# 06_GBE_SDCARD.net
KiCad netlist of a schematic drawn in Altium Designer
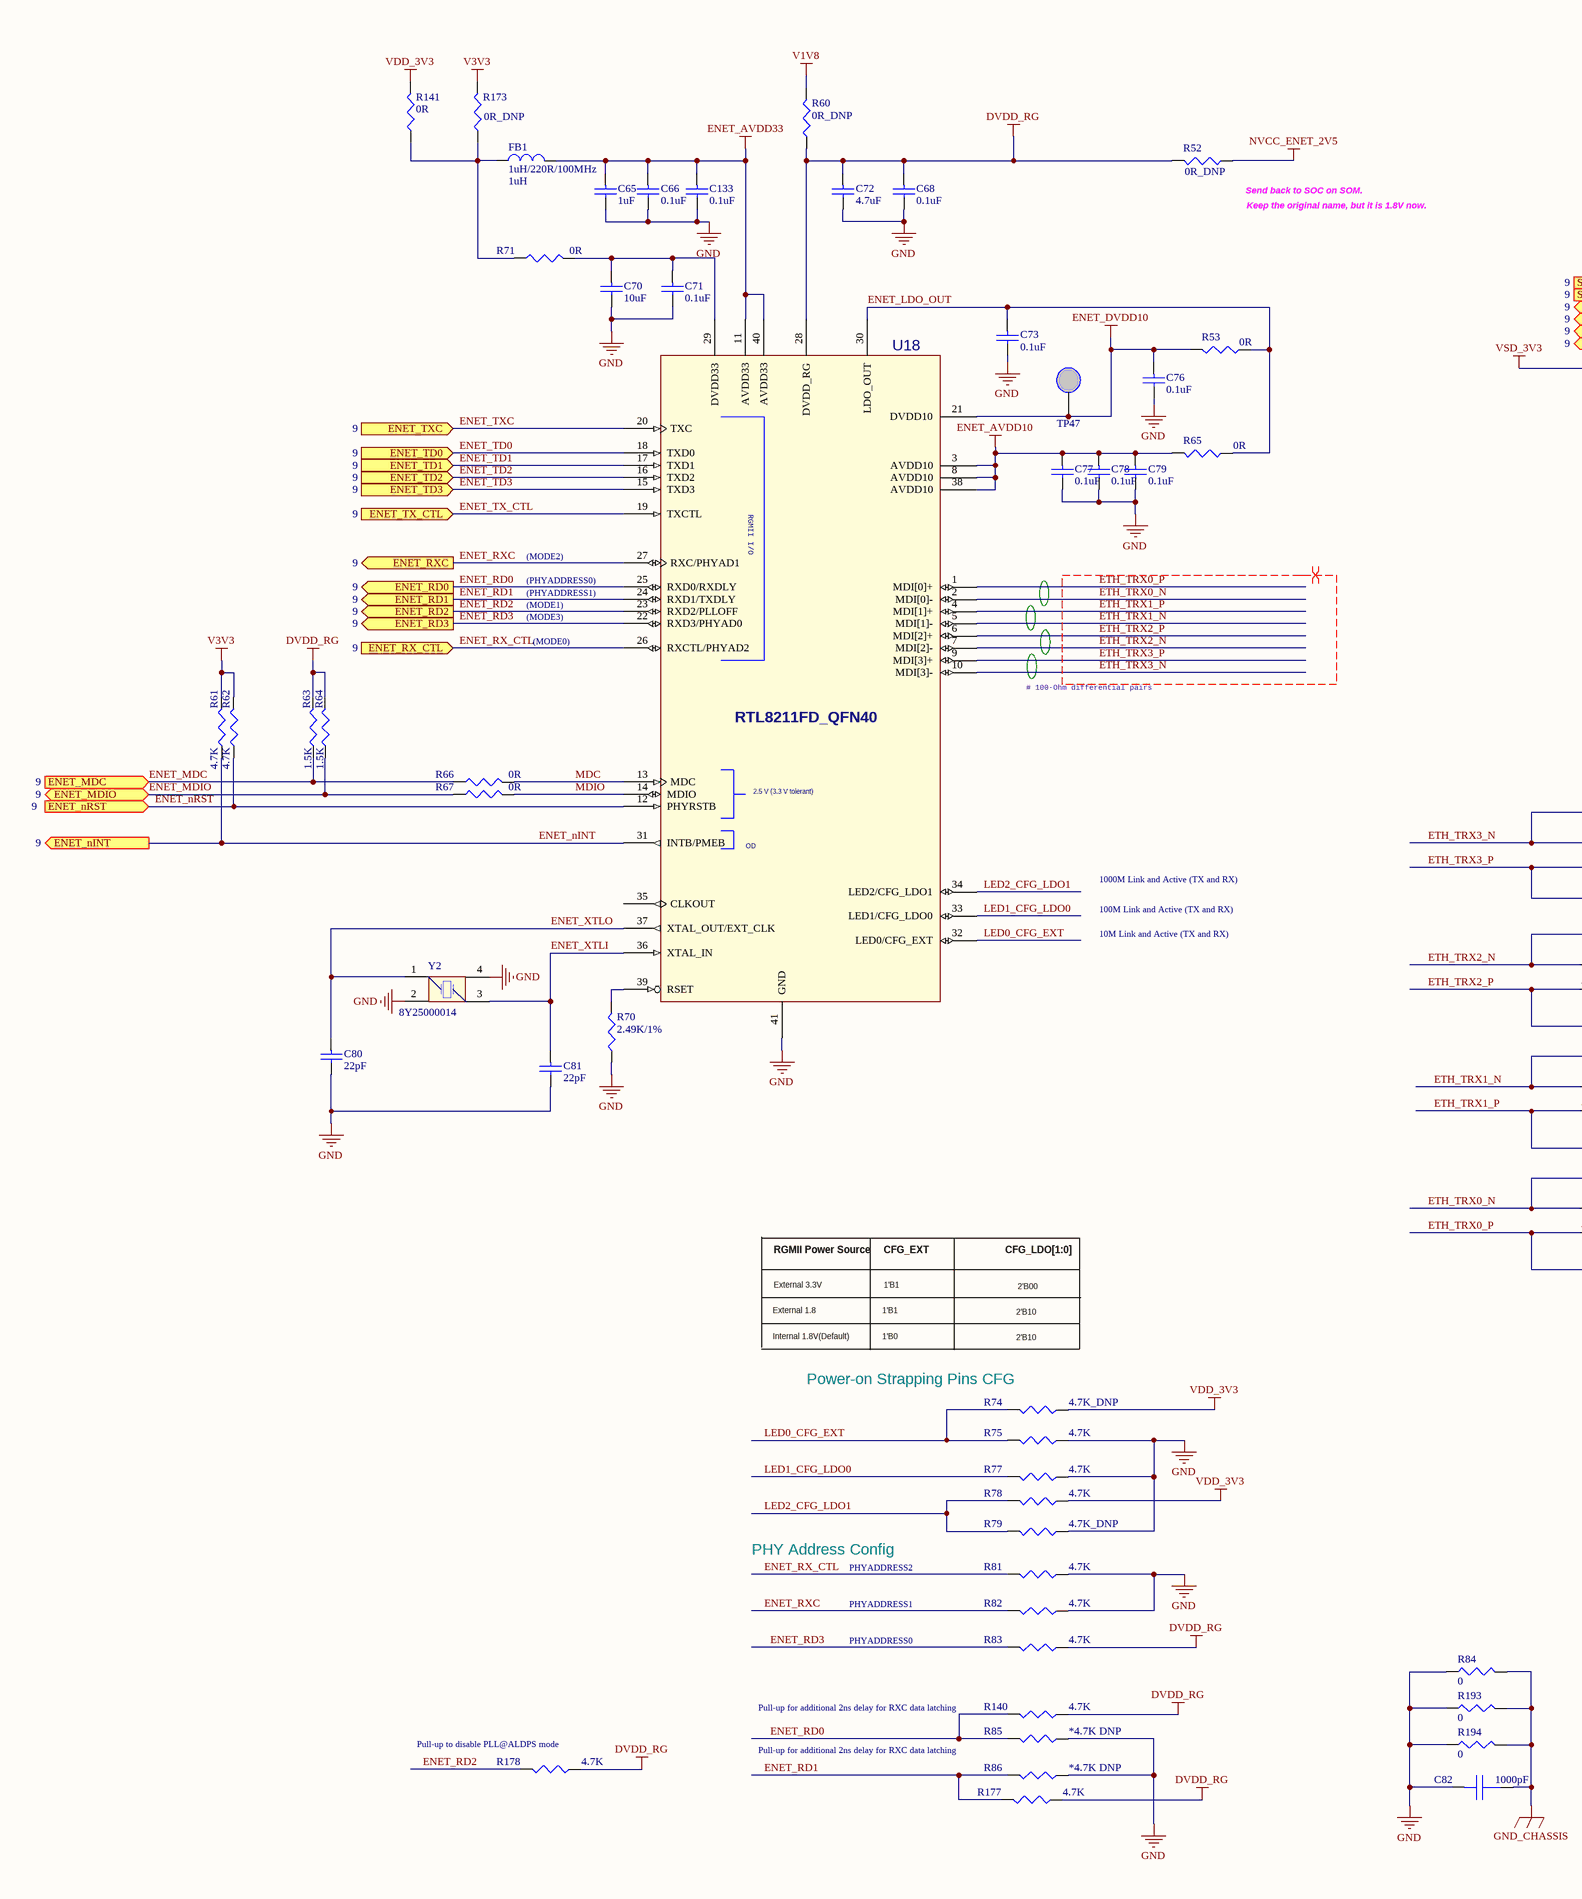
[diagram p0: 06_GBE_SDCARD.SchDoc, left]
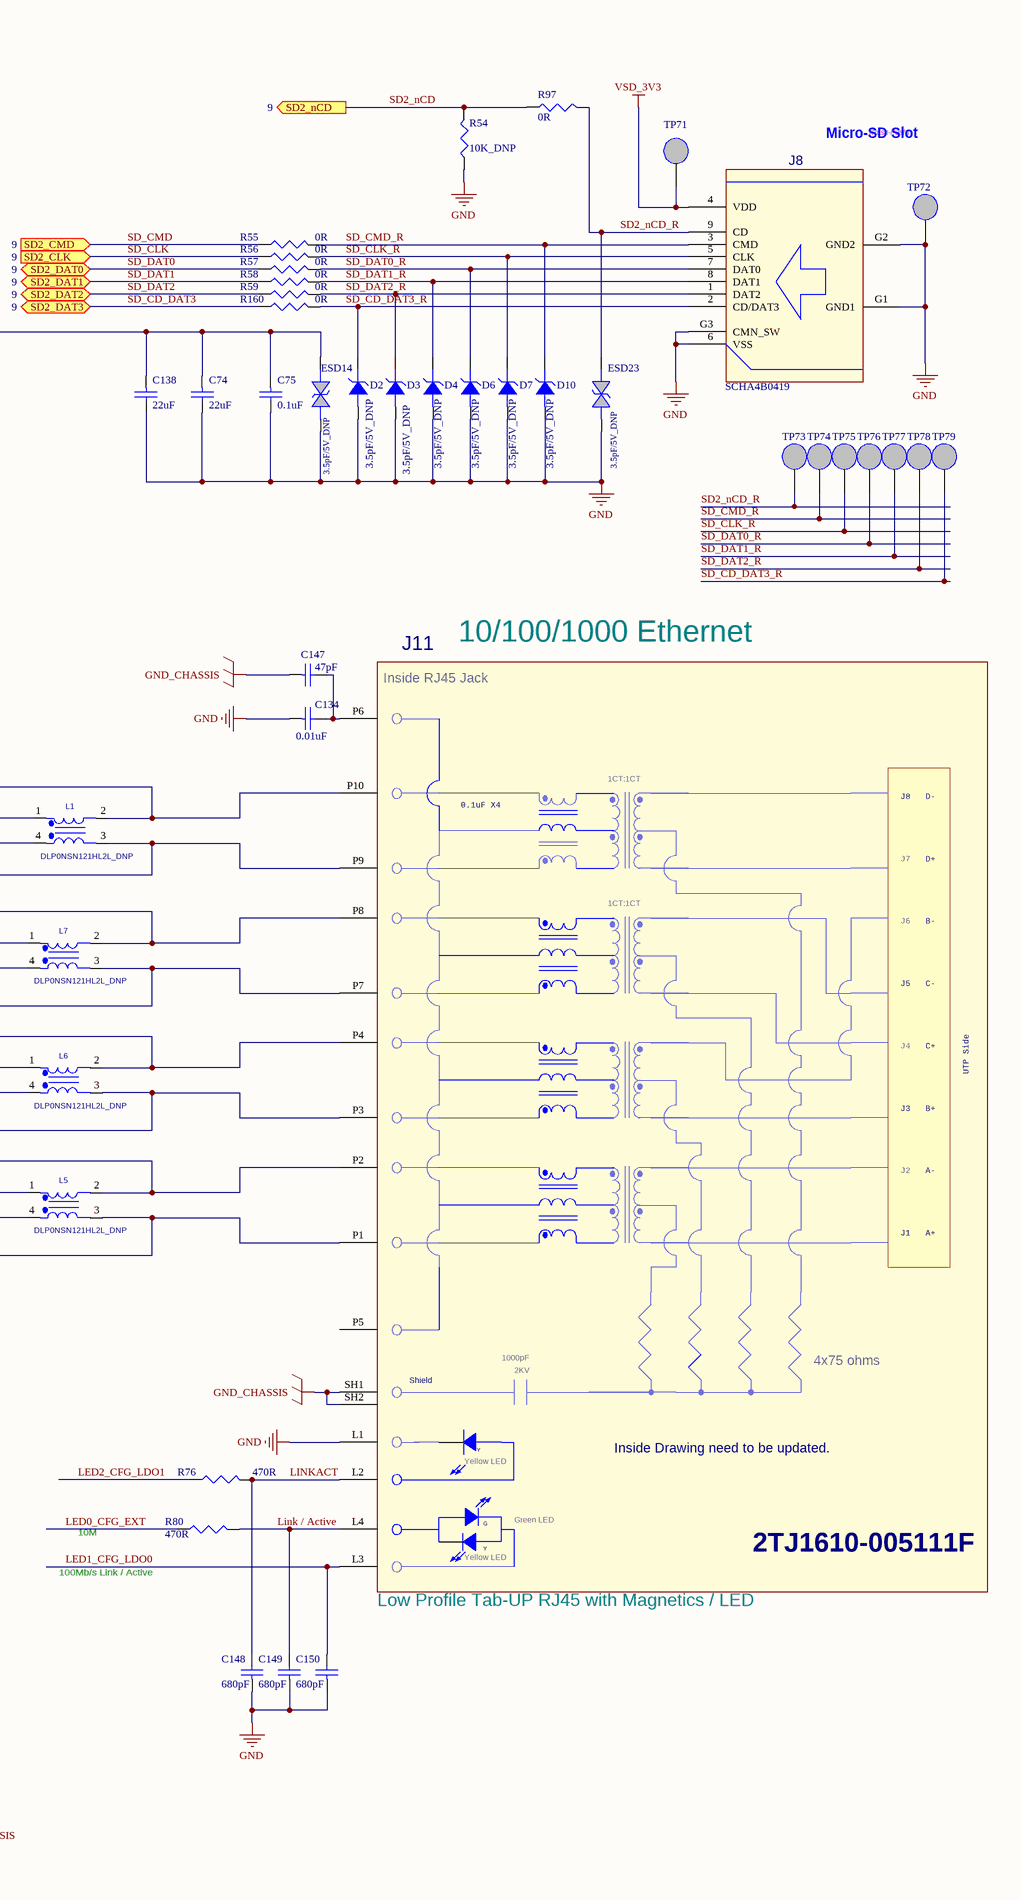
[diagram p1: 06_GBE_SDCARD.SchDoc, right]

(export (version "E")
  (design (tool "Eeschema 10.0.6"))
  (components
    (comp (ref "C65")
      (value "1uF")
      (footprint "0201")
      (description "CAP CER 1UF 6.3V 20% X5R 0201")
      (fields (field (name "MPN") "C0603X5R0J105M030BC") (field (name "Comment") "1uF/6.3V"))
      (libsource (lib "links") (part "CAP_0201_1.0uF"))
    )
    (comp (ref "C66")
      (value "0.1uF")
      (footprint "0201")
      (description "CAP CER 0.1UF 10V 10% X5R 0201")
      (fields (field (name "MPN") "C0603X5R1A104K030BC") (field (name "Comment") "0.1uF/10V"))
      (libsource (lib "links") (part "CAP_0201_0.1uF"))
    )
    (comp (ref "C68")
      (value "0.1uF")
      (footprint "0201")
      (description "CAP CER 0.1UF 10V 10% X5R 0201")
      (fields (field (name "MPN") "C0603X5R1A104K030BC") (field (name "Comment") "0.1uF/10V"))
      (libsource (lib "links") (part "CAP_0201_0.1uF"))
    )
    (comp (ref "C70")
      (value "10uF")
      (footprint "0402")
      (description "CAP CER 10UF 10V 20% X5R 0402")
      (fields (field (name "MPN") "CL05A106MP5NUNC") (field (name "Comment") "10uF/10V"))
      (libsource (lib "links") (part "CAP_0402_10uF"))
    )
    (comp (ref "C71")
      (value "0.1uF")
      (footprint "0201")
      (description "CAP CER 0.1UF 10V 10% X5R 0201")
      (fields (field (name "MPN") "C0603X5R1A104K030BC") (field (name "Comment") "0.1uF/10V"))
      (libsource (lib "links") (part "CAP_0201_0.1uF"))
    )
    (comp (ref "C72")
      (value "4.7uF")
      (footprint "0402")
      (description "CAP CER 4.7UF 10V 20% X5R 0402")
      (fields (field (name "MPN") "C1005X5R1A475M050BC") (field (name "Comment") "4.7uF/10V"))
      (libsource (lib "links") (part "CAP_0402_4.7uF"))
    )
    (comp (ref "C73")
      (value "0.1uF")
      (footprint "0201")
      (description "CAP CER 0.1UF 10V 10% X5R 0201")
      (fields (field (name "MPN") "C0603X5R1A104K030BC") (field (name "Comment") "0.1uF/10V"))
      (libsource (lib "links") (part "CAP_0201_0.1uF"))
    )
    (comp (ref "C74")
      (value "22uF")
      (footprint "0603")
      (description "CAP CER 22UF 6.3V 10% X5R 0603")
      (fields (field (name "MPN") "CL10A226KQ8NRNE") (field (name "Comment") "22uF/10V"))
      (libsource (lib "links") (part "CAP_0603_22uF"))
    )
    (comp (ref "C75")
      (value "0.1uF")
      (footprint "0201")
      (description "CAP CER 0.1UF 10V 10% X5R 0201")
      (fields (field (name "MPN") "C0603X5R1A104K030BC") (field (name "Comment") "0.1uF/10V"))
      (libsource (lib "links") (part "CAP_0201_0.1uF"))
    )
    (comp (ref "C76")
      (value "0.1uF")
      (footprint "0201")
      (description "CAP CER 0.1UF 10V 10% X5R 0201")
      (fields (field (name "MPN") "C0603X5R1A104K030BC") (field (name "Comment") "0.1uF/10V"))
      (libsource (lib "links") (part "CAP_0201_0.1uF"))
    )
    (comp (ref "C77")
      (value "0.1uF")
      (footprint "0201")
      (description "CAP CER 0.1UF 10V 10% X5R 0201")
      (fields (field (name "MPN") "C0603X5R1A104K030BC") (field (name "Comment") "0.1uF/10V"))
      (libsource (lib "links") (part "CAP_0201_0.1uF"))
    )
    (comp (ref "C78")
      (value "0.1uF")
      (footprint "0201")
      (description "CAP CER 0.1UF 10V 10% X5R 0201")
      (fields (field (name "MPN") "C0603X5R1A104K030BC") (field (name "Comment") "0.1uF/10V"))
      (libsource (lib "links") (part "CAP_0201_0.1uF"))
    )
    (comp (ref "C79")
      (value "0.1uF")
      (footprint "0201")
      (description "CAP CER 0.1UF 10V 10% X5R 0201")
      (fields (field (name "MPN") "C0603X5R1A104K030BC") (field (name "Comment") "0.1uF/10V"))
      (libsource (lib "links") (part "CAP_0201_0.1uF"))
    )
    (comp (ref "C80")
      (value "22pF")
      (footprint "0201")
      (description "CAP CER 22pF 6.3V 2% C0G NP0 0201")
      (fields (field (name "MPN") "GJM0335C0J220GB01D") (field (name "Comment") "22pF/6.3V"))
      (libsource (lib "links") (part "CAP_0201_22pF"))
    )
    (comp (ref "C81")
      (value "22pF")
      (footprint "0201")
      (description "CAP CER 22pF 6.3V 2% C0G NP0 0201")
      (fields (field (name "MPN") "GJM0335C0J220GB01D") (field (name "Comment") "22pF/6.3V"))
      (libsource (lib "links") (part "CAP_0201_22pF"))
    )
    (comp (ref "C82")
      (value "1000pF")
      (footprint "1206")
      (description "CAP CER 1000PF 2KV 10% 1206 X7R")
      (fields (field (name "MPN") "CC1206KKX7RDBB102") (field (name "Comment") "1000pF/2KV"))
      (libsource (lib "links") (part "CAP_1206_1000pF_2KV"))
    )
    (comp (ref "C133")
      (value "0.1uF")
      (footprint "0201")
      (description "CAP CER 0.1UF 10V 10% X5R 0201")
      (fields (field (name "MPN") "C0603X5R1A104K030BC") (field (name "Comment") "0.1uF/10V"))
      (libsource (lib "links") (part "CAP_0201_0.1uF"))
    )
    (comp (ref "C134")
      (value "0.01uF")
      (footprint "0201")
      (description "CAP CHIP 0.01UF 25V(+-10%,X7R,0201)")
      (fields (field (name "MPN") "GRM033R71E103K") (field (name "Comment") "0.01uF/25V"))
      (libsource (lib "links") (part "CAP_0201_0.1uF"))
    )
    (comp (ref "C138")
      (value "22uF")
      (footprint "0603")
      (description "CAP CER 22UF 6.3V 10% X5R 0603")
      (fields (field (name "MPN") "CL10A226KQ8NRNE") (field (name "Comment") "22uF/10V"))
      (libsource (lib "links") (part "CAP_0603_22uF"))
    )
    (comp (ref "C147")
      (value "47pF")
      (footprint "0201")
      (description "CAP CER 47PF 25V 0201")
      (fields (field (name "MPN") "GRM0335C1E470FA01D") (field (name "Comment") "47pF/25V"))
      (libsource (lib "links") (part "CAP_0201_47pF"))
    )
    (comp (ref "C148")
      (value "680pF")
      (footprint "0201")
      (description "CAP CHIP 680PF 25V(+-10%,X7R,0201)")
      (fields (field (name "MPN") "GRM033R71E681K") (field (name "Comment") "680PF 25V"))
      (libsource (lib "links") (part "CAP_0201_1.0nF"))
    )
    (comp (ref "C149")
      (value "680pF")
      (footprint "0201")
      (description "CAP CHIP 680PF 25V(+-10%,X7R,0201)")
      (fields (field (name "MPN") "GRM033R71E681K") (field (name "Comment") "680PF 25V"))
      (libsource (lib "links") (part "CAP_0201_1.0nF"))
    )
    (comp (ref "C150")
      (value "680pF")
      (footprint "0201")
      (description "CAP CHIP 680PF 25V(+-10%,X7R,0201)")
      (fields (field (name "MPN") "GRM033R71E681K") (field (name "Comment") "680PF 25V"))
      (libsource (lib "links") (part "CAP_0201_1.0nF"))
    )
    (comp (ref "D2")
      (value "3.5pF/5V_DNP")
      (footprint "0201-Diode")
      (description "TVS DIODE 3V ST0201")
      (fields (field (name "MPN") "DESD5V0V1BCSP-7"))
      (libsource (lib "links") (part "Diode-ESDALC6V1-1U2"))
    )
    (comp (ref "D3")
      (value "3.5pF/5V_DNP")
      (footprint "0201-Diode")
      (description "TVS DIODE 3V ST0201")
      (fields (field (name "MPN") "DESD5V0V1BCSP-7"))
      (libsource (lib "links") (part "Diode-ESDALC6V1-1U2"))
    )
    (comp (ref "D4")
      (value "3.5pF/5V_DNP")
      (footprint "0201-Diode")
      (description "TVS DIODE 3V ST0201")
      (fields (field (name "MPN") "DESD5V0V1BCSP-7"))
      (libsource (lib "links") (part "Diode-ESDALC6V1-1U2"))
    )
    (comp (ref "D6")
      (value "3.5pF/5V_DNP")
      (footprint "0201-Diode")
      (description "TVS DIODE 3V ST0201")
      (fields (field (name "MPN") "DESD5V0V1BCSP-7"))
      (libsource (lib "links") (part "Diode-ESDALC6V1-1U2"))
    )
    (comp (ref "D7")
      (value "3.5pF/5V_DNP")
      (footprint "0201-Diode")
      (description "TVS DIODE 3V ST0201")
      (fields (field (name "MPN") "DESD5V0V1BCSP-7"))
      (libsource (lib "links") (part "Diode-ESDALC6V1-1U2"))
    )
    (comp (ref "D10")
      (value "3.5pF/5V_DNP")
      (footprint "0201-Diode")
      (description "TVS DIODE 3V ST0201")
      (fields (field (name "MPN") "DESD5V0V1BCSP-7"))
      (libsource (lib "links") (part "Diode-ESDALC6V1-1U2"))
    )
    (comp (ref "ESD14")
      (value "3.5pF/5V_DNP")
      (footprint "0201")
      (description "DIODE TVS 15kV 10V 50A 8pF SMT RoHS")
      (fields (field (name "MPN") "DESD5V0V1BCSP-7"))
      (libsource (lib "links") (part "DIODE BI-DIR TRIG"))
    )
    (comp (ref "ESD23")
      (value "3.5pF/5V_DNP")
      (footprint "0201")
      (description "DIODE TVS 15kV 10V 50A 8pF SMT RoHS")
      (fields (field (name "MPN") "DESD5V0V1BCSP-7"))
      (libsource (lib "links") (part "DIODE BI-DIR TRIG"))
    )
    (comp (ref "FB1")
      (value "1uH/220R/100MHz")
      (footprint "0603")
      (description "FERRITE CHIP 220 OHM 2.0A 0603")
      (fields (field (name "ALTIUM_VALUE") "1uH") (field (name "MPN") "BLM18EG221SN1D"))
      (libsource (lib "SpacePark") (part "INDUCTOR_BLM18EG221SN1D"))
    )
    (comp (ref "J8")
      (value "SCHA4B0419")
      (footprint "CON9_SDCARD_8PIN_SCHA4B0419")
      (description "CON SD CARD PUSH SMT 1.32mm 8pin")
      (fields (field (name "SUPPLIER PART NUMBER 1") "SCHA4B0419"))
      (libsource (lib "SpacePark") (part "CONN_MICRO_SDCARD_8P_ALPS"))
    )
    (comp (ref "J11")
      (value "2TJ1610-005111F")
      (footprint "RJ45-LED-2TJ1610-005111F")
      (description "CON 10 RJ45 SKT RA TH WITH G/Y LEDS 50MIL SP 611H -- 120L")
      (libsource (lib "SpacePark") (part "RJ45_Singatron_2TJ1610-005111F"))
    )
    (comp (ref "L1")
      (value "DLP0NSN121HL2L_DNP")
      (footprint "PL4-DLP0NSN121HL2L")
      (description "EMI FLTR DLP0NSN121HL2L(120,20%,90MA)")
      (fields (field (name "MPN") "DLP0NSN121HL2L"))
      (libsource (lib "SpacePark") (part "IND_CMC_DLW21"))
    )
    (comp (ref "L5")
      (value "DLP0NSN121HL2L_DNP")
      (footprint "PL4-DLP0NSN121HL2L")
      (description "EMI FLTR DLP0NSN121HL2L(120,20%,90MA)")
      (fields (field (name "MPN") "DLP0NSN121HL2L"))
      (libsource (lib "SpacePark") (part "IND_CMC_DLW21"))
    )
    (comp (ref "L6")
      (value "DLP0NSN121HL2L_DNP")
      (footprint "PL4-DLP0NSN121HL2L")
      (description "EMI FLTR DLP0NSN121HL2L(120,20%,90MA)")
      (fields (field (name "MPN") "DLP0NSN121HL2L"))
      (libsource (lib "SpacePark") (part "IND_CMC_DLW21"))
    )
    (comp (ref "L7")
      (value "DLP0NSN121HL2L_DNP")
      (footprint "PL4-DLP0NSN121HL2L")
      (description "EMI FLTR DLP0NSN121HL2L(120,20%,90MA)")
      (fields (field (name "MPN") "DLP0NSN121HL2L"))
      (libsource (lib "SpacePark") (part "IND_CMC_DLW21"))
    )
    (comp (ref "R52")
      (value "0R_DNP")
      (footprint "0201")
      (description "RES SMD 0.0OHM JUMPER 1/20W 0201")
      (fields (field (name "MPN") "ERJ-1GN0R00C"))
      (libsource (lib "links") (part "R_0201_0"))
    )
    (comp (ref "R53")
      (value "0R")
      (footprint "0201")
      (description "RES SMD 0.0OHM JUMPER 1/20W 0201")
      (fields (field (name "MPN") "ERJ-1GN0R00C"))
      (libsource (lib "links") (part "R_0201_0"))
    )
    (comp (ref "R54")
      (value "10K_DNP")
      (footprint "0201")
      (description "RES SMD 10K OHM JUMPER 1/20W  0201")
      (fields (field (name "MPN") "ERJ-1GEF103C") (field (name "Comment") "10K"))
      (libsource (lib "links") (part "R_0201_10K"))
    )
    (comp (ref "R55")
      (value "0R")
      (footprint "0201")
      (description "RES SMD 0.0OHM JUMPER 1/20W 0201")
      (fields (field (name "MPN") "ERJ-1GN0R00C"))
      (libsource (lib "links") (part "R_0201_0"))
    )
    (comp (ref "R56")
      (value "0R")
      (footprint "0201")
      (description "RES SMD 0.0OHM JUMPER 1/20W 0201")
      (fields (field (name "MPN") "ERJ-1GN0R00C"))
      (libsource (lib "links") (part "R_0201_0"))
    )
    (comp (ref "R57")
      (value "0R")
      (footprint "0201")
      (description "RES SMD 0.0OHM JUMPER 1/20W 0201")
      (fields (field (name "MPN") "ERJ-1GN0R00C"))
      (libsource (lib "links") (part "R_0201_0"))
    )
    (comp (ref "R58")
      (value "0R")
      (footprint "0201")
      (description "RES SMD 0.0OHM JUMPER 1/20W 0201")
      (fields (field (name "MPN") "ERJ-1GN0R00C"))
      (libsource (lib "links") (part "R_0201_0"))
    )
    (comp (ref "R59")
      (value "0R")
      (footprint "0201")
      (description "RES SMD 0.0OHM JUMPER 1/20W 0201")
      (fields (field (name "MPN") "ERJ-1GN0R00C"))
      (libsource (lib "links") (part "R_0201_0"))
    )
    (comp (ref "R60")
      (value "0R_DNP")
      (footprint "0201")
      (description "RES SMD 0.0OHM JUMPER 1/20W 0201")
      (fields (field (name "MPN") "ERJ-1GN0R00C"))
      (libsource (lib "links") (part "R_0201_0"))
    )
    (comp (ref "R61")
      (value "4.7K")
      (footprint "0201")
      (description "RES SMD 4.7K OHM 1% 1/20W 0201")
      (fields (field (name "MPN") "ERJ-1GEF4701C"))
      (libsource (lib "links") (part "R_0201_4.7K"))
    )
    (comp (ref "R62")
      (value "4.7K")
      (footprint "0201")
      (description "RES SMD 4.7K OHM 1% 1/20W 0201")
      (fields (field (name "MPN") "ERJ-1GEF4701C"))
      (libsource (lib "links") (part "R_0201_4.7K"))
    )
    (comp (ref "R63")
      (value "1.5K")
      (footprint "0201")
      (description "RES SMD 1.5K OHM JUMPER 1/20W  0201")
      (fields (field (name "MPN") "ERJ-1GEJ6152C"))
      (libsource (lib "links") (part "R_0201_1.5K"))
    )
    (comp (ref "R64")
      (value "1.5K")
      (footprint "0201")
      (description "RES SMD 1.5K OHM JUMPER 1/20W  0201")
      (fields (field (name "MPN") "ERJ-1GEJ6152C"))
      (libsource (lib "links") (part "R_0201_1.5K"))
    )
    (comp (ref "R65")
      (value "0R")
      (footprint "0201")
      (description "RES SMD 0.0OHM JUMPER 1/20W 0201")
      (fields (field (name "MPN") "ERJ-1GN0R00C"))
      (libsource (lib "links") (part "R_0201_0"))
    )
    (comp (ref "R66")
      (value "0R")
      (footprint "0201")
      (description "RES SMD 0.0OHM JUMPER 1/20W 0201")
      (fields (field (name "MPN") "ERJ-1GN0R00C"))
      (libsource (lib "links") (part "R_0201_0"))
    )
    (comp (ref "R67")
      (value "0R")
      (footprint "0201")
      (description "RES SMD 0.0OHM JUMPER 1/20W 0201")
      (fields (field (name "MPN") "ERJ-1GN0R00C"))
      (libsource (lib "links") (part "R_0201_0"))
    )
    (comp (ref "R70")
      (value "2.49K/1%")
      (footprint "0201")
      (description "RES SMD 2.49K OHM 1% 1/20W 0201")
      (fields (field (name "MPN") "RC0201FR-132K49L"))
      (libsource (lib "links") (part "R_0201_2.49K"))
    )
    (comp (ref "R71")
      (value "0R")
      (footprint "0201")
      (description "RES SMD 0.0OHM JUMPER 1/20W 0201")
      (fields (field (name "MPN") "ERJ-1GN0R00C"))
      (libsource (lib "links") (part "R_0201_0"))
    )
    (comp (ref "R74")
      (value "4.7K_DNP")
      (footprint "0201")
      (description "RES SMD 4.7K OHM 1% 1/20W 0201")
      (fields (field (name "MPN") "ERJ-1GEF4701C"))
      (libsource (lib "links") (part "R_0201_4.7K"))
    )
    (comp (ref "R75")
      (value "4.7K")
      (footprint "0201")
      (description "RES SMD 4.7K OHM 1% 1/20W 0201")
      (fields (field (name "MPN") "ERJ-1GEF4701C"))
      (libsource (lib "links") (part "R_0201_4.7K"))
    )
    (comp (ref "R76")
      (value "470R")
      (footprint "0201")
      (description "RES CHIP 470 1/20W +-5% (0201)")
      (fields (field (name "MPN") "RC0201JR-07470RL"))
      (libsource (lib "links") (part "R_0201_300"))
    )
    (comp (ref "R77")
      (value "4.7K")
      (footprint "0201")
      (description "RES SMD 4.7K OHM 1% 1/20W 0201")
      (fields (field (name "MPN") "ERJ-1GEF4701C"))
      (libsource (lib "links") (part "R_0201_4.7K"))
    )
    (comp (ref "R78")
      (value "4.7K")
      (footprint "0201")
      (description "RES SMD 4.7K OHM 1% 1/20W 0201")
      (fields (field (name "MPN") "ERJ-1GEF4701C"))
      (libsource (lib "links") (part "R_0201_4.7K"))
    )
    (comp (ref "R79")
      (value "4.7K_DNP")
      (footprint "0201")
      (description "RES SMD 4.7K OHM 1% 1/20W 0201")
      (fields (field (name "MPN") "ERJ-1GEF4701C"))
      (libsource (lib "links") (part "R_0201_4.7K"))
    )
    (comp (ref "R80")
      (value "470R")
      (footprint "0201")
      (description "RES CHIP 470 1/20W +-5% (0201)")
      (fields (field (name "MPN") "RC0201JR-07470RL"))
      (libsource (lib "links") (part "R_0201_300"))
    )
    (comp (ref "R81")
      (value "4.7K")
      (footprint "0201")
      (description "RES SMD 4.7K OHM 1% 1/20W 0201")
      (fields (field (name "MPN") "ERJ-1GEF4701C"))
      (libsource (lib "links") (part "R_0201_4.7K"))
    )
    (comp (ref "R82")
      (value "4.7K")
      (footprint "0201")
      (description "RES SMD 4.7K OHM 1% 1/20W 0201")
      (fields (field (name "MPN") "ERJ-1GEF4701C"))
      (libsource (lib "links") (part "R_0201_4.7K"))
    )
    (comp (ref "R83")
      (value "4.7K")
      (footprint "0201")
      (description "RES SMD 4.7K OHM 1% 1/20W 0201")
      (fields (field (name "MPN") "ERJ-1GEF4701C"))
      (libsource (lib "links") (part "R_0201_4.7K"))
    )
    (comp (ref "R84")
      (value "0")
      (footprint "0805")
      (description "RES SMD 0 OHM 1% 1/2W 0805")
      (fields (field (name "Comment") "R_0805_0"))
      (libsource (lib "links") (part "R_0805_0"))
    )
    (comp (ref "R85")
      (value "*4.7K DNP")
      (footprint "0201")
      (description "RES SMD 4.7K OHM 1% 1/20W 0201")
      (fields (field (name "MPN") "ERJ-1GEF4701C") (field (name "Comment") "4.7K"))
      (libsource (lib "links") (part "R_0201_4.7K"))
    )
    (comp (ref "R86")
      (value "*4.7K DNP")
      (footprint "0201")
      (description "RES SMD 4.7K OHM 1% 1/20W 0201")
      (fields (field (name "MPN") "ERJ-1GEF4701C") (field (name "Comment") "4.7K"))
      (libsource (lib "links") (part "R_0201_4.7K"))
    )
    (comp (ref "R97")
      (value "0R")
      (footprint "0201")
      (description "RES SMD 0.0OHM JUMPER 1/20W 0201")
      (fields (field (name "MPN") "ERJ-1GN0R00C") (field (name "Comment") "0R_DNP"))
      (libsource (lib "links") (part "R_0201_0"))
    )
    (comp (ref "R140")
      (value "4.7K")
      (footprint "0201")
      (description "RES SMD 4.7K OHM 1% 1/20W 0201")
      (fields (field (name "MPN") "ERJ-1GEF4701C") (field (name "Comment") "4.7K_DNP"))
      (libsource (lib "links") (part "R_0201_4.7K"))
    )
    (comp (ref "R141")
      (value "0R")
      (footprint "0201")
      (description "RES SMD 0.0OHM JUMPER 1/20W 0201")
      (fields (field (name "MPN") "ERJ-1GN0R00C"))
      (libsource (lib "links") (part "R_0201_0"))
    )
    (comp (ref "R160")
      (value "0R")
      (footprint "0201")
      (description "RES SMD 0.0OHM JUMPER 1/20W 0201")
      (fields (field (name "MPN") "ERJ-1GN0R00C"))
      (libsource (lib "links") (part "R_0201_0"))
    )
    (comp (ref "R173")
      (value "0R_DNP")
      (footprint "0201")
      (description "RES SMD 0.0OHM JUMPER 1/20W 0201")
      (fields (field (name "MPN") "ERJ-1GN0R00C"))
      (libsource (lib "links") (part "R_0201_0"))
    )
    (comp (ref "R177")
      (value "4.7K")
      (footprint "0201")
      (description "RES SMD 4.7K OHM 1% 1/20W 0201")
      (fields (field (name "MPN") "ERJ-1GEF4701C") (field (name "Comment") "4.7K_DNP"))
      (libsource (lib "links") (part "R_0201_4.7K"))
    )
    (comp (ref "R178")
      (value "4.7K")
      (footprint "0201")
      (description "RES SMD 4.7K OHM 1% 1/20W 0201")
      (fields (field (name "MPN") "ERJ-1GEF4701C"))
      (libsource (lib "links") (part "R_0201_4.7K"))
    )
    (comp (ref "R193")
      (value "0")
      (footprint "0805")
      (description "RES SMD 0 OHM 1% 1/2W 0805")
      (fields (field (name "Comment") "R_0805_0"))
      (libsource (lib "links") (part "R_0805_0"))
    )
    (comp (ref "R194")
      (value "0")
      (footprint "0805")
      (description "RES SMD 0 OHM 1% 1/2W 0805")
      (fields (field (name "Comment") "R_0805_0"))
      (libsource (lib "links") (part "R_0805_0"))
    )
    (comp (ref "TP47")
      (value "TP NM")
      (footprint "TP_SMD")
      (description "TEST POIN")
      (libsource (lib "links") (part "TP"))
    )
    (comp (ref "TP71")
      (value "TP NM")
      (footprint "TP_SMD")
      (description "TEST POIN")
      (libsource (lib "links") (part "TP"))
    )
    (comp (ref "TP72")
      (value "TP NM")
      (footprint "TP_SMD")
      (description "TEST POIN")
      (libsource (lib "links") (part "TP"))
    )
    (comp (ref "TP73")
      (value "TP NM")
      (footprint "TP3050")
      (description "TEST POIN")
      (libsource (lib "links") (part "TP"))
    )
    (comp (ref "TP74")
      (value "TP NM")
      (footprint "TP3050")
      (description "TEST POIN")
      (libsource (lib "links") (part "TP"))
    )
    (comp (ref "TP75")
      (value "TP NM")
      (footprint "TP3050")
      (description "TEST POIN")
      (libsource (lib "links") (part "TP"))
    )
    (comp (ref "TP76")
      (value "TP NM")
      (footprint "TP3050")
      (description "TEST POIN")
      (libsource (lib "links") (part "TP"))
    )
    (comp (ref "TP77")
      (value "TP NM")
      (footprint "TP3050")
      (description "TEST POIN")
      (libsource (lib "links") (part "TP"))
    )
    (comp (ref "TP78")
      (value "TP NM")
      (footprint "TP3050")
      (description "TEST POIN")
      (libsource (lib "links") (part "TP"))
    )
    (comp (ref "TP79")
      (value "TP NM")
      (footprint "TP3050")
      (description "TEST POIN")
      (libsource (lib "links") (part "TP"))
    )
    (comp (ref "U18")
      (value "RTL8211FD_QFN40")
      (footprint "QFN40-0_4-5X5-H0_9MM")
      (description "IC XCVR ETHERNET PHY 10/100/1000G-BIT 3.3V QFN40")
      (libsource (lib "SpacePark") (part "RTL8211FD_QFN40"))
    )
    (comp (ref "Y2")
      (value "8Y25000014")
      (footprint "DFN130P250X50-4N")
      (description "Crystal 25.0000MHz 30ppm 10pF 60 Ohm -40蚓 - 125蚓 Surface Mount 4-SMD, No Lead (DFN, LCC)")
      (libsource (lib "links") (part "XTAL_25MHZ_ABM10AIG-25.000MHZ-4Z-T3"))
    )
  )
  (nets
    (net (code "1") (name "/ENET_LDO_OUT") (class "Default")
      (node (ref "C73") (pin "1") (pinfunction "1_1") (pintype "passive"))
      (node (ref "R53") (pin "1") (pintype "passive"))
      (node (ref "R65") (pin "1") (pintype "passive"))
      (node (ref "U18") (pin "30") (pinfunction "LDO_OUT_30") (pintype "power_in"))
    )
    (net (code "2") (name "/ENET_MDC") (class "Default")
      (node (ref "R63") (pin "1") (pintype "passive"))
      (node (ref "R66") (pin "1") (pintype "passive"))
    )
    (net (code "3") (name "/ENET_MDIO") (class "Default")
      (node (ref "R64") (pin "1") (pintype "passive"))
      (node (ref "R67") (pin "1") (pintype "passive"))
    )
    (net (code "4") (name "/ENET_RD0") (class "Default")
      (node (ref "R140") (pin "2") (pintype "passive"))
      (node (ref "R85") (pin "2") (pintype "passive"))
      (node (ref "U18") (pin "25") (pinfunction "RXD0/RXDLY_25") (pintype "bidirectional"))
    )
    (net (code "5") (name "/ENET_RD1") (class "Default")
      (node (ref "R177") (pin "2") (pintype "passive"))
      (node (ref "R86") (pin "2") (pintype "passive"))
      (node (ref "U18") (pin "24") (pinfunction "RXD1/TXDLY_24") (pintype "bidirectional"))
    )
    (net (code "6") (name "/ENET_RD2") (class "Default")
      (node (ref "R178") (pin "2") (pintype "passive"))
      (node (ref "U18") (pin "23") (pinfunction "RXD2/PLLOFF_23") (pintype "bidirectional"))
    )
    (net (code "7") (name "/ENET_RD3") (class "Default")
      (node (ref "R83") (pin "2") (pintype "passive"))
      (node (ref "U18") (pin "22") (pinfunction "RXD3/PHYAD0_22") (pintype "bidirectional"))
    )
    (net (code "8") (name "/ENET_RXC") (class "Default")
      (node (ref "R82") (pin "2") (pintype "passive"))
      (node (ref "U18") (pin "27") (pinfunction "RXC/PHYAD1_27") (pintype "bidirectional"))
    )
    (net (code "9") (name "/ENET_RX_CTL") (class "Default")
      (node (ref "R81") (pin "2") (pintype "passive"))
      (node (ref "U18") (pin "26") (pinfunction "RXCTL/PHYAD2_26") (pintype "bidirectional"))
    )
    (net (code "10") (name "/ENET_TD0") (class "Default")
      (node (ref "U18") (pin "18") (pinfunction "TXD0_18") (pintype "input"))
    )
    (net (code "11") (name "/ENET_TD1") (class "Default")
      (node (ref "U18") (pin "17") (pinfunction "TXD1_17") (pintype "input"))
    )
    (net (code "12") (name "/ENET_TD2") (class "Default")
      (node (ref "U18") (pin "16") (pinfunction "TXD2_16") (pintype "input"))
    )
    (net (code "13") (name "/ENET_TD3") (class "Default")
      (node (ref "U18") (pin "15") (pinfunction "TXD3_15") (pintype "input"))
    )
    (net (code "14") (name "/ENET_TXC") (class "Default")
      (node (ref "U18") (pin "20") (pinfunction "TXC_20") (pintype "input"))
    )
    (net (code "15") (name "/ENET_TX_CTL") (class "Default")
      (node (ref "U18") (pin "19") (pinfunction "TXCTL_19") (pintype "input"))
    )
    (net (code "16") (name "/ENET_XTLI") (class "Default")
      (node (ref "C81") (pin "1") (pinfunction "1_1") (pintype "passive"))
      (node (ref "U18") (pin "36") (pinfunction "XTAL_IN_36") (pintype "input"))
      (node (ref "Y2") (pin "3") (pinfunction "OSC3_3") (pintype "passive"))
    )
    (net (code "17") (name "/ENET_XTLO") (class "Default")
      (node (ref "C80") (pin "1") (pinfunction "1_1") (pintype "passive"))
      (node (ref "U18") (pin "37") (pinfunction "XTAL_OUT/EXT_CLK_37") (pintype "output"))
      (node (ref "Y2") (pin "1") (pinfunction "OSC1_1") (pintype "passive"))
    )
    (net (code "18") (name "/ENET_nINT") (class "Default")
      (node (ref "R61") (pin "1") (pintype "passive"))
      (node (ref "U18") (pin "31") (pinfunction "INTB/PMEB_31") (pintype "output"))
    )
    (net (code "19") (name "/ENET_nRST") (class "Default")
      (node (ref "R62") (pin "1") (pintype "passive"))
      (node (ref "U18") (pin "12") (pinfunction "PHYRSTB_12") (pintype "input"))
    )
    (net (code "20") (name "/ETH_TRX0_N") (class "Default")
      (node (ref "J11") (pin "P2") (pinfunction "P2_P2") (pintype "passive"))
      (node (ref "L5") (pin "1") (pinfunction "1_1") (pintype "passive"))
      (node (ref "L5") (pin "2") (pinfunction "2_2") (pintype "passive"))
      (node (ref "U18") (pin "2") (pinfunction "MDI[0]-_2") (pintype "bidirectional"))
    )
    (net (code "21") (name "/ETH_TRX0_P") (class "Default")
      (node (ref "J11") (pin "P1") (pinfunction "P1_P1") (pintype "passive"))
      (node (ref "L5") (pin "3") (pinfunction "3_3") (pintype "passive"))
      (node (ref "L5") (pin "4") (pinfunction "4_4") (pintype "passive"))
      (node (ref "U18") (pin "1") (pinfunction "MDI[0]+_1") (pintype "bidirectional"))
    )
    (net (code "22") (name "/ETH_TRX1_N") (class "Default")
      (node (ref "J11") (pin "P4") (pinfunction "P4_P4") (pintype "passive"))
      (node (ref "L6") (pin "1") (pinfunction "1_1") (pintype "passive"))
      (node (ref "L6") (pin "2") (pinfunction "2_2") (pintype "passive"))
      (node (ref "U18") (pin "5") (pinfunction "MDI[1]-_5") (pintype "bidirectional"))
    )
    (net (code "23") (name "/ETH_TRX1_P") (class "Default")
      (node (ref "J11") (pin "P3") (pinfunction "P3_P3") (pintype "passive"))
      (node (ref "L6") (pin "3") (pinfunction "3_3") (pintype "passive"))
      (node (ref "L6") (pin "4") (pinfunction "4_4") (pintype "passive"))
      (node (ref "U18") (pin "4") (pinfunction "MDI[1]+_4") (pintype "bidirectional"))
    )
    (net (code "24") (name "/ETH_TRX2_N") (class "Default")
      (node (ref "J11") (pin "P8") (pinfunction "P8_P8") (pintype "passive"))
      (node (ref "L7") (pin "1") (pinfunction "1_1") (pintype "passive"))
      (node (ref "L7") (pin "2") (pinfunction "2_2") (pintype "passive"))
      (node (ref "U18") (pin "7") (pinfunction "MDI[2]-_7") (pintype "bidirectional"))
    )
    (net (code "25") (name "/ETH_TRX2_P") (class "Default")
      (node (ref "J11") (pin "P7") (pinfunction "P7_P7") (pintype "passive"))
      (node (ref "L7") (pin "3") (pinfunction "3_3") (pintype "passive"))
      (node (ref "L7") (pin "4") (pinfunction "4_4") (pintype "passive"))
      (node (ref "U18") (pin "6") (pinfunction "MDI[2]+_6") (pintype "bidirectional"))
    )
    (net (code "26") (name "/ETH_TRX3_N") (class "Default")
      (node (ref "J11") (pin "P10") (pinfunction "P10_P10") (pintype "passive"))
      (node (ref "L1") (pin "1") (pinfunction "1_1") (pintype "passive"))
      (node (ref "L1") (pin "2") (pinfunction "2_2") (pintype "passive"))
      (node (ref "U18") (pin "10") (pinfunction "MDI[3]-_10") (pintype "bidirectional"))
    )
    (net (code "27") (name "/ETH_TRX3_P") (class "Default")
      (node (ref "J11") (pin "P9") (pinfunction "P9_P9") (pintype "passive"))
      (node (ref "L1") (pin "3") (pinfunction "3_3") (pintype "passive"))
      (node (ref "L1") (pin "4") (pinfunction "4_4") (pintype "passive"))
      (node (ref "U18") (pin "9") (pinfunction "MDI[3]+_9") (pintype "bidirectional"))
    )
    (net (code "28") (name "/LED0_CFG_EXT") (class "Default")
      (node (ref "R74") (pin "2") (pintype "passive"))
      (node (ref "R75") (pin "2") (pintype "passive"))
      (node (ref "R80") (pin "1") (pintype "passive"))
      (node (ref "U18") (pin "32") (pinfunction "LED0/CFG_EXT_32") (pintype "bidirectional"))
    )
    (net (code "29") (name "/LED1_CFG_LDO0") (class "Default")
      (node (ref "C150") (pin "2") (pinfunction "2_2") (pintype "passive"))
      (node (ref "J11") (pin "L3") (pinfunction "L3_L3") (pintype "passive"))
      (node (ref "R77") (pin "2") (pintype "passive"))
      (node (ref "U18") (pin "33") (pinfunction "LED1/CFG_LDO0_33") (pintype "bidirectional"))
    )
    (net (code "30") (name "/LED2_CFG_LDO1") (class "Default")
      (node (ref "R76") (pin "1") (pintype "passive"))
      (node (ref "R78") (pin "2") (pintype "passive"))
      (node (ref "R79") (pin "2") (pintype "passive"))
      (node (ref "U18") (pin "34") (pinfunction "LED2/CFG_LDO1_34") (pintype "bidirectional"))
    )
    (net (code "31") (name "/LINKACT") (class "Default")
      (node (ref "C148") (pin "2") (pinfunction "2_2") (pintype "passive"))
      (node (ref "J11") (pin "L2") (pinfunction "L2_L2") (pintype "passive"))
      (node (ref "R76") (pin "2") (pintype "passive"))
    )
    (net (code "32") (name "/Link {slash} Active") (class "Default")
      (node (ref "C149") (pin "2") (pinfunction "2_2") (pintype "passive"))
      (node (ref "J11") (pin "L4") (pinfunction "L4_L4") (pintype "passive"))
      (node (ref "R80") (pin "2") (pintype "passive"))
    )
    (net (code "33") (name "/MDC") (class "Default")
      (node (ref "R66") (pin "2") (pintype "passive"))
      (node (ref "U18") (pin "13") (pinfunction "MDC_13") (pintype "input"))
    )
    (net (code "34") (name "/MDIO") (class "Default")
      (node (ref "R67") (pin "2") (pintype "passive"))
      (node (ref "U18") (pin "14") (pinfunction "MDIO_14") (pintype "bidirectional"))
    )
    (net (code "35") (name "/SD2_nCD") (class "Default")
      (node (ref "R54") (pin "2") (pintype "passive"))
      (node (ref "R97") (pin "2") (pintype "passive"))
    )
    (net (code "36") (name "/SD2_nCD_R") (class "Default")
      (node (ref "ESD23") (pin "2") (pinfunction "2_2") (pintype "passive"))
      (node (ref "J8") (pin "9") (pinfunction "CD_9") (pintype "passive"))
      (node (ref "R97") (pin "1") (pintype "passive"))
      (node (ref "TP73") (pin "1") (pinfunction "1_1") (pintype "passive"))
    )
    (net (code "37") (name "/SD_CD_DAT3") (class "Default") (node (ref "R160") (pin "1") (pintype "passive")))
    (net (code "38") (name "/SD_CD_DAT3_R") (class "Default")
      (node (ref "D2") (pin "K") (pinfunction "K_K") (pintype "passive"))
      (node (ref "J8") (pin "2") (pinfunction "CD/DAT3_2") (pintype "passive"))
      (node (ref "R160") (pin "2") (pintype "passive"))
      (node (ref "TP79") (pin "1") (pinfunction "1_1") (pintype "passive"))
    )
    (net (code "39") (name "/SD_CLK") (class "Default") (node (ref "R56") (pin "1") (pintype "passive")))
    (net (code "40") (name "/SD_CLK_R") (class "Default")
      (node (ref "D7") (pin "K") (pinfunction "K_K") (pintype "passive"))
      (node (ref "J8") (pin "5") (pinfunction "CLK_5") (pintype "passive"))
      (node (ref "R56") (pin "2") (pintype "passive"))
      (node (ref "TP75") (pin "1") (pinfunction "1_1") (pintype "passive"))
    )
    (net (code "41") (name "/SD_CMD") (class "Default") (node (ref "R55") (pin "1") (pintype "passive")))
    (net (code "42") (name "/SD_CMD_R") (class "Default")
      (node (ref "D10") (pin "K") (pinfunction "K_K") (pintype "passive"))
      (node (ref "J8") (pin "3") (pinfunction "CMD_3") (pintype "passive"))
      (node (ref "R55") (pin "2") (pintype "passive"))
      (node (ref "TP74") (pin "1") (pinfunction "1_1") (pintype "passive"))
    )
    (net (code "43") (name "/SD_DAT0") (class "Default") (node (ref "R57") (pin "1") (pintype "passive")))
    (net (code "44") (name "/SD_DAT0_R") (class "Default")
      (node (ref "D6") (pin "K") (pinfunction "K_K") (pintype "passive"))
      (node (ref "J8") (pin "7") (pinfunction "DAT0_7") (pintype "passive"))
      (node (ref "R57") (pin "2") (pintype "passive"))
      (node (ref "TP76") (pin "1") (pinfunction "1_1") (pintype "passive"))
    )
    (net (code "45") (name "/SD_DAT1") (class "Default") (node (ref "R58") (pin "1") (pintype "passive")))
    (net (code "46") (name "/SD_DAT1_R") (class "Default")
      (node (ref "D4") (pin "K") (pinfunction "K_K") (pintype "passive"))
      (node (ref "J8") (pin "8") (pinfunction "DAT1_8") (pintype "passive"))
      (node (ref "R58") (pin "2") (pintype "passive"))
      (node (ref "TP77") (pin "1") (pinfunction "1_1") (pintype "passive"))
    )
    (net (code "47") (name "/SD_DAT2") (class "Default") (node (ref "R59") (pin "1") (pintype "passive")))
    (net (code "48") (name "/SD_DAT2_R") (class "Default")
      (node (ref "D3") (pin "K") (pinfunction "K_K") (pintype "passive"))
      (node (ref "J8") (pin "1") (pinfunction "DAT2_1") (pintype "passive"))
      (node (ref "R59") (pin "2") (pintype "passive"))
      (node (ref "TP78") (pin "1") (pinfunction "1_1") (pintype "passive"))
    )
    (net (code "49") (name "DVDD_RG") (class "Default")
      (node (ref "C68") (pin "1") (pinfunction "1_1") (pintype "passive"))
      (node (ref "C72") (pin "1") (pinfunction "1_1") (pintype "passive"))
      (node (ref "R140") (pin "1") (pintype "passive"))
      (node (ref "R177") (pin "1") (pintype "passive"))
      (node (ref "R178") (pin "1") (pintype "passive"))
      (node (ref "R52") (pin "2") (pintype "passive"))
      (node (ref "R60") (pin "1") (pintype "passive"))
      (node (ref "R63") (pin "2") (pintype "passive"))
      (node (ref "R64") (pin "2") (pintype "passive"))
      (node (ref "R83") (pin "1") (pintype "passive"))
      (node (ref "U18") (pin "28") (pinfunction "DVDD_RG_28") (pintype "power_in"))
    )
    (net (code "50") (name "ENET_AVDD10") (class "Default")
      (node (ref "C77") (pin "1") (pinfunction "1_1") (pintype "passive"))
      (node (ref "C78") (pin "1") (pinfunction "1_1") (pintype "passive"))
      (node (ref "C79") (pin "1") (pinfunction "1_1") (pintype "passive"))
      (node (ref "R65") (pin "2") (pintype "passive"))
      (node (ref "U18") (pin "3") (pinfunction "AVDD10_3") (pintype "power_in"))
      (node (ref "U18") (pin "38") (pinfunction "AVDD10_38") (pintype "power_in"))
      (node (ref "U18") (pin "8") (pinfunction "AVDD10_8") (pintype "power_in"))
    )
    (net (code "51") (name "ENET_AVDD33") (class "Default")
      (node (ref "C133") (pin "1") (pinfunction "1_1") (pintype "passive"))
      (node (ref "C65") (pin "1") (pinfunction "1_1") (pintype "passive"))
      (node (ref "C66") (pin "1") (pinfunction "1_1") (pintype "passive"))
      (node (ref "FB1") (pin "2") (pinfunction "2_2") (pintype "passive"))
      (node (ref "U18") (pin "11") (pinfunction "AVDD33_11") (pintype "power_in"))
      (node (ref "U18") (pin "40") (pinfunction "AVDD33_40") (pintype "power_in"))
    )
    (net (code "52") (name "ENET_DVDD10") (class "Default")
      (node (ref "C76") (pin "1") (pinfunction "1_1") (pintype "passive"))
      (node (ref "R53") (pin "2") (pintype "passive"))
      (node (ref "TP47") (pin "1") (pinfunction "1_1") (pintype "passive"))
      (node (ref "U18") (pin "21") (pinfunction "DVDD10_21") (pintype "power_in"))
    )
    (net (code "53") (name "GND") (class "Default")
      (node (ref "C133") (pin "2") (pinfunction "2_2") (pintype "passive"))
      (node (ref "C134") (pin "1") (pinfunction "1_1") (pintype "passive"))
      (node (ref "C138") (pin "2") (pinfunction "2_2") (pintype "passive"))
      (node (ref "C148") (pin "1") (pinfunction "1_1") (pintype "passive"))
      (node (ref "C149") (pin "1") (pinfunction "1_1") (pintype "passive"))
      (node (ref "C150") (pin "1") (pinfunction "1_1") (pintype "passive"))
      (node (ref "C65") (pin "2") (pinfunction "2_2") (pintype "passive"))
      (node (ref "C66") (pin "2") (pinfunction "2_2") (pintype "passive"))
      (node (ref "C68") (pin "2") (pinfunction "2_2") (pintype "passive"))
      (node (ref "C70") (pin "2") (pinfunction "2_2") (pintype "passive"))
      (node (ref "C71") (pin "2") (pinfunction "2_2") (pintype "passive"))
      (node (ref "C72") (pin "2") (pinfunction "2_2") (pintype "passive"))
      (node (ref "C73") (pin "2") (pinfunction "2_2") (pintype "passive"))
      (node (ref "C74") (pin "2") (pinfunction "2_2") (pintype "passive"))
      (node (ref "C75") (pin "2") (pinfunction "2_2") (pintype "passive"))
      (node (ref "C76") (pin "2") (pinfunction "2_2") (pintype "passive"))
      (node (ref "C77") (pin "2") (pinfunction "2_2") (pintype "passive"))
      (node (ref "C78") (pin "2") (pinfunction "2_2") (pintype "passive"))
      (node (ref "C79") (pin "2") (pinfunction "2_2") (pintype "passive"))
      (node (ref "C80") (pin "2") (pinfunction "2_2") (pintype "passive"))
      (node (ref "C81") (pin "2") (pinfunction "2_2") (pintype "passive"))
      (node (ref "C82") (pin "1") (pinfunction "1_1") (pintype "passive"))
      (node (ref "D10") (pin "A") (pinfunction "A_A") (pintype "passive"))
      (node (ref "D2") (pin "A") (pinfunction "A_A") (pintype "passive"))
      (node (ref "D3") (pin "A") (pinfunction "A_A") (pintype "passive"))
      (node (ref "D4") (pin "A") (pinfunction "A_A") (pintype "passive"))
      (node (ref "D6") (pin "A") (pinfunction "A_A") (pintype "passive"))
      (node (ref "D7") (pin "A") (pinfunction "A_A") (pintype "passive"))
      (node (ref "ESD14") (pin "1") (pinfunction "1_1") (pintype "passive"))
      (node (ref "ESD23") (pin "1") (pinfunction "1_1") (pintype "passive"))
      (node (ref "J11") (pin "L1") (pinfunction "L1_L1") (pintype "passive"))
      (node (ref "J8") (pin "6") (pinfunction "VSS_6") (pintype "power_in"))
      (node (ref "J8") (pin "G1") (pinfunction "GND1_G1") (pintype "power_in"))
      (node (ref "J8") (pin "G2") (pinfunction "GND2_G2") (pintype "power_in"))
      (node (ref "J8") (pin "G3") (pinfunction "CMN_SW_G3") (pintype "power_in"))
      (node (ref "R193") (pin "1") (pintype "passive"))
      (node (ref "R194") (pin "1") (pintype "passive"))
      (node (ref "R54") (pin "1") (pintype "passive"))
      (node (ref "R70") (pin "1") (pintype "passive"))
      (node (ref "R75") (pin "1") (pintype "passive"))
      (node (ref "R77") (pin "1") (pintype "passive"))
      (node (ref "R79") (pin "1") (pintype "passive"))
      (node (ref "R81") (pin "1") (pintype "passive"))
      (node (ref "R82") (pin "1") (pintype "passive"))
      (node (ref "R84") (pin "1") (pintype "passive"))
      (node (ref "R85") (pin "1") (pintype "passive"))
      (node (ref "R86") (pin "1") (pintype "passive"))
      (node (ref "TP72") (pin "1") (pinfunction "1_1") (pintype "passive"))
      (node (ref "U18") (pin "41") (pinfunction "GND_41") (pintype "power_in"))
      (node (ref "Y2") (pin "2") (pinfunction "2_2") (pintype "passive"))
      (node (ref "Y2") (pin "4") (pinfunction "4_4") (pintype "passive"))
    )
    (net (code "54") (name "GND_CHASSIS") (class "Default")
      (node (ref "C147") (pin "1") (pinfunction "1_1") (pintype "passive"))
      (node (ref "C82") (pin "2") (pinfunction "2_2") (pintype "passive"))
      (node (ref "J11") (pin "SH1") (pinfunction "SH1_SH1") (pintype "power_in"))
      (node (ref "J11") (pin "SH2") (pinfunction "SH2_SH2") (pintype "power_in"))
      (node (ref "R193") (pin "2") (pintype "passive"))
      (node (ref "R194") (pin "2") (pintype "passive"))
      (node (ref "R84") (pin "2") (pintype "passive"))
    )
    (net (code "55") (name "NVCC_ENET_2V5") (class "Default")
      (node (ref "R52") (pin "1") (pintype "passive"))
    )
    (net (code "56") (name "Net-(C134-Pad2)") (class "Default")
      (node (ref "C134") (pin "2") (pinfunction "2_2") (pintype "passive"))
      (node (ref "C147") (pin "2") (pinfunction "2_2") (pintype "passive"))
      (node (ref "J11") (pin "P6") (pinfunction "P6_P6") (pintype "passive"))
    )
    (net (code "57") (name "Net-(FB1-Pad1)") (class "Default")
      (node (ref "FB1") (pin "1") (pinfunction "1_1") (pintype "passive"))
      (node (ref "R141") (pin "1") (pintype "passive"))
      (node (ref "R173") (pin "1") (pintype "passive"))
      (node (ref "R71") (pin "1") (pintype "passive"))
    )
    (net (code "58") (name "Net-(U18-DVDD33)") (class "Default")
      (node (ref "C70") (pin "1") (pinfunction "1_1") (pintype "passive"))
      (node (ref "C71") (pin "1") (pinfunction "1_1") (pintype "passive"))
      (node (ref "R71") (pin "2") (pintype "passive"))
      (node (ref "U18") (pin "29") (pinfunction "DVDD33_29") (pintype "power_in"))
    )
    (net (code "59") (name "Net-(U18-RSET)") (class "Default")
      (node (ref "R70") (pin "2") (pintype "passive"))
      (node (ref "U18") (pin "39") (pinfunction "RSET_39") (pintype "input"))
    )
    (net (code "60") (name "V1V8") (class "Default") (node (ref "R60") (pin "2") (pintype "passive")))
    (net (code "61") (name "V3V3") (class "Default")
      (node (ref "R173") (pin "2") (pintype "passive"))
      (node (ref "R61") (pin "2") (pintype "passive"))
      (node (ref "R62") (pin "2") (pintype "passive"))
    )
    (net (code "62") (name "VDD_3V3") (class "Default")
      (node (ref "R141") (pin "2") (pintype "passive"))
      (node (ref "R74") (pin "1") (pintype "passive"))
      (node (ref "R78") (pin "1") (pintype "passive"))
    )
    (net (code "63") (name "VSD_3V3") (class "Default")
      (node (ref "C138") (pin "1") (pinfunction "1_1") (pintype "passive"))
      (node (ref "C74") (pin "1") (pinfunction "1_1") (pintype "passive"))
      (node (ref "C75") (pin "1") (pinfunction "1_1") (pintype "passive"))
      (node (ref "ESD14") (pin "2") (pinfunction "2_2") (pintype "passive"))
      (node (ref "J8") (pin "4") (pinfunction "VDD_4") (pintype "power_in"))
      (node (ref "TP71") (pin "1") (pinfunction "1_1") (pintype "passive"))
    )
    (net (code "64") (name "unconnected-(J11-PadP5)") (class "Default")
      (node (ref "J11") (pin "P5") (pinfunction "P5_P5") (pintype "passive"))
    )
    (net (code "65") (name "unconnected-(U18-CLKOUT-Pad35)") (class "Default")
      (node (ref "U18") (pin "35") (pinfunction "CLKOUT_35") (pintype "output"))
    )
  )
)
